# ROMmulti_final_rev01.net
KiCad netlist of a schematic drawn in EAGLE
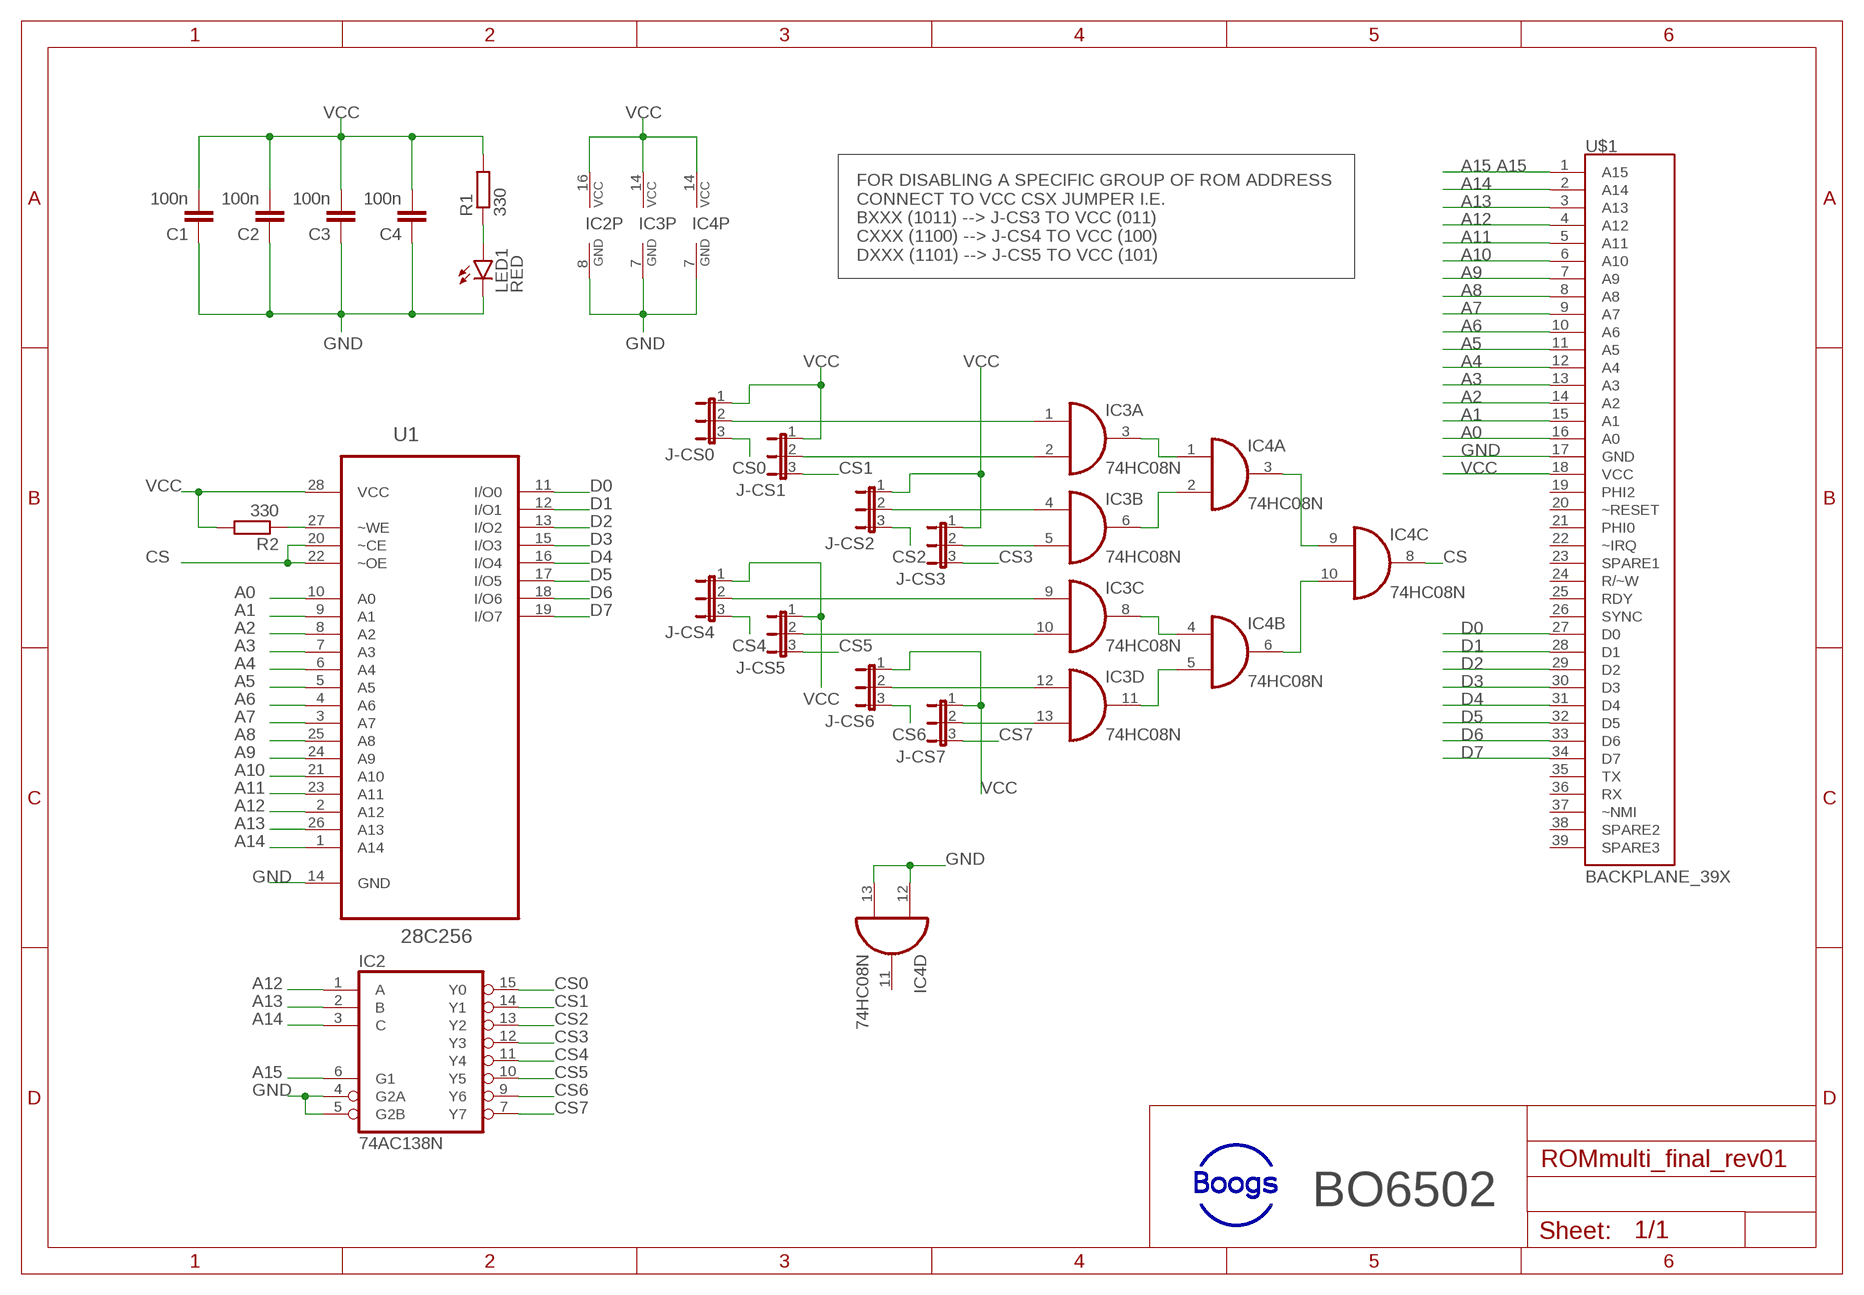
[diagram p0: schematic, sheet 1]

(export (version "E")
  (design (tool "Eeschema 10.0.6"))
  (components
    (comp (ref "C1")
      (value "100n")
      (footprint "eagle-import:C025-025X050")
      (libsource (lib "eagle-import") (part "C-EU025-025X050"))
    )
    (comp (ref "C2")
      (value "100n")
      (footprint "eagle-import:C025-025X050")
      (libsource (lib "eagle-import") (part "C-EU025-025X050"))
    )
    (comp (ref "C3")
      (value "100n")
      (footprint "eagle-import:C025-025X050")
      (libsource (lib "eagle-import") (part "C-EU025-025X050"))
    )
    (comp (ref "C4")
      (value "100n")
      (footprint "eagle-import:C025-025X050")
      (libsource (lib "eagle-import") (part "C-EU025-025X050"))
    )
    (comp (ref "IC2")
      (value "74AC138N")
      (footprint "eagle-import:DIL16")
      (libsource (lib "eagle-import") (part "74138NAC"))
    )
    (comp (ref "IC3")
      (value "74HC08N")
      (footprint "eagle-import:DIL14")
      (libsource (lib "eagle-import") (part "7408NHC"))
    )
    (comp (ref "IC4")
      (value "74HC08N")
      (footprint "eagle-import:DIL14")
      (libsource (lib "eagle-import") (part "7408NHC"))
    )
    (comp (ref "J-CS0")
      (value "J-CS0")
      (footprint "eagle-import:JP2")
      (libsource (lib "eagle-import") (part "JP2E"))
    )
    (comp (ref "J-CS1")
      (value "J-CS1")
      (footprint "eagle-import:JP2")
      (libsource (lib "eagle-import") (part "JP2E"))
    )
    (comp (ref "J-CS2")
      (value "J-CS2")
      (footprint "eagle-import:JP2")
      (libsource (lib "eagle-import") (part "JP2E"))
    )
    (comp (ref "J-CS3")
      (value "J-CS3")
      (footprint "eagle-import:JP2")
      (libsource (lib "eagle-import") (part "JP2E"))
    )
    (comp (ref "J-CS4")
      (value "J-CS4")
      (footprint "eagle-import:JP2")
      (libsource (lib "eagle-import") (part "JP2E"))
    )
    (comp (ref "J-CS5")
      (value "J-CS5")
      (footprint "eagle-import:JP2")
      (libsource (lib "eagle-import") (part "JP2E"))
    )
    (comp (ref "J-CS6")
      (value "J-CS6")
      (footprint "eagle-import:JP2")
      (libsource (lib "eagle-import") (part "JP2E"))
    )
    (comp (ref "J-CS7")
      (value "J-CS7")
      (footprint "eagle-import:JP2")
      (libsource (lib "eagle-import") (part "JP2E"))
    )
    (comp (ref "LED1")
      (value "RED")
      (footprint "eagle-import:LED5MM")
      (libsource (lib "eagle-import") (part "LED5MM"))
    )
    (comp (ref "R1")
      (value "330")
      (footprint "eagle-import:0207_10")
      (libsource (lib "eagle-import") (part "R-EU_0207/10"))
    )
    (comp (ref "R2")
      (value "330")
      (footprint "eagle-import:0207_10")
      (libsource (lib "eagle-import") (part "R-EU_0207/10"))
    )
    (comp (ref "U$1")
      (value "BACKPLANE_39X")
      (footprint "eagle-import:BP_39X")
      (fields (field (name "A15") "A15"))
      (libsource (lib "eagle-import") (part "BACKPLANE_39X"))
    )
    (comp (ref "U1")
      (value "28C256")
      (footprint "eagle-import:DIP254P1524X482-28")
      (fields (field (name "MF") "Microchip") (field (name "MP") "AT28C256-15PU"))
      (libsource (lib "eagle-import") (part "AT28C256-15PU"))
    )
  )
  (nets
    (net (code "1") (name "/A0") (class "Default")
      (node (ref "U$1") (pin "16") (pinfunction "A0_16") (pintype "bidirectional"))
      (node (ref "U1") (pin "10") (pinfunction "A0_10") (pintype "input"))
    )
    (net (code "2") (name "/A1") (class "Default")
      (node (ref "U$1") (pin "15") (pinfunction "A1_15") (pintype "bidirectional"))
      (node (ref "U1") (pin "9") (pinfunction "A1_9") (pintype "input"))
    )
    (net (code "3") (name "/A2") (class "Default")
      (node (ref "U$1") (pin "14") (pinfunction "A2_14") (pintype "bidirectional"))
      (node (ref "U1") (pin "8") (pinfunction "A2_8") (pintype "input"))
    )
    (net (code "4") (name "/A3") (class "Default")
      (node (ref "U$1") (pin "13") (pinfunction "A3_13") (pintype "bidirectional"))
      (node (ref "U1") (pin "7") (pinfunction "A3_7") (pintype "input"))
    )
    (net (code "5") (name "/A4") (class "Default")
      (node (ref "U$1") (pin "12") (pinfunction "A4_12") (pintype "bidirectional"))
      (node (ref "U1") (pin "6") (pinfunction "A4_6") (pintype "input"))
    )
    (net (code "6") (name "/A5") (class "Default")
      (node (ref "U$1") (pin "11") (pinfunction "A5_11") (pintype "bidirectional"))
      (node (ref "U1") (pin "5") (pinfunction "A5_5") (pintype "input"))
    )
    (net (code "7") (name "/A6") (class "Default")
      (node (ref "U$1") (pin "10") (pinfunction "A6_10") (pintype "bidirectional"))
      (node (ref "U1") (pin "4") (pinfunction "A6_4") (pintype "input"))
    )
    (net (code "8") (name "/A7") (class "Default")
      (node (ref "U$1") (pin "9") (pinfunction "A7_9") (pintype "bidirectional"))
      (node (ref "U1") (pin "3") (pinfunction "A7_3") (pintype "input"))
    )
    (net (code "9") (name "/A8") (class "Default")
      (node (ref "U$1") (pin "8") (pinfunction "A8_8") (pintype "bidirectional"))
      (node (ref "U1") (pin "25") (pinfunction "A8_25") (pintype "input"))
    )
    (net (code "10") (name "/A9") (class "Default")
      (node (ref "U$1") (pin "7") (pinfunction "A9_7") (pintype "bidirectional"))
      (node (ref "U1") (pin "24") (pinfunction "A9_24") (pintype "input"))
    )
    (net (code "11") (name "/A10") (class "Default")
      (node (ref "U$1") (pin "6") (pinfunction "A10_6") (pintype "bidirectional"))
      (node (ref "U1") (pin "21") (pinfunction "A10_21") (pintype "input"))
    )
    (net (code "12") (name "/A11") (class "Default")
      (node (ref "U$1") (pin "5") (pinfunction "A11_5") (pintype "bidirectional"))
      (node (ref "U1") (pin "23") (pinfunction "A11_23") (pintype "input"))
    )
    (net (code "13") (name "/A12") (class "Default")
      (node (ref "IC2") (pin "1") (pinfunction "A_1") (pintype "input"))
      (node (ref "U$1") (pin "4") (pinfunction "A12_4") (pintype "bidirectional"))
      (node (ref "U1") (pin "2") (pinfunction "A12_2") (pintype "input"))
    )
    (net (code "14") (name "/A13") (class "Default")
      (node (ref "IC2") (pin "2") (pinfunction "B_2") (pintype "input"))
      (node (ref "U$1") (pin "3") (pinfunction "A13_3") (pintype "bidirectional"))
      (node (ref "U1") (pin "26") (pinfunction "A13_26") (pintype "input"))
    )
    (net (code "15") (name "/A14") (class "Default")
      (node (ref "IC2") (pin "3") (pinfunction "C_3") (pintype "input"))
      (node (ref "U$1") (pin "2") (pinfunction "A14_2") (pintype "bidirectional"))
      (node (ref "U1") (pin "1") (pinfunction "A14_1") (pintype "input"))
    )
    (net (code "16") (name "/A15") (class "Default")
      (node (ref "IC2") (pin "6") (pinfunction "G1_6") (pintype "input"))
      (node (ref "U$1") (pin "1") (pinfunction "A15_1") (pintype "bidirectional"))
    )
    (net (code "17") (name "/CS") (class "Default")
      (node (ref "IC4") (pin "8") (pinfunction "O_8") (pintype "output"))
      (node (ref "U1") (pin "20") (pinfunction "~{CE}_20") (pintype "input"))
      (node (ref "U1") (pin "22") (pinfunction "~{OE}_22") (pintype "input"))
    )
    (net (code "18") (name "/CS0") (class "Default")
      (node (ref "IC2") (pin "15") (pinfunction "Y0_15") (pintype "output"))
      (node (ref "J-CS0") (pin "3") (pinfunction "3_3") (pintype "passive"))
    )
    (net (code "19") (name "/CS1") (class "Default")
      (node (ref "IC2") (pin "14") (pinfunction "Y1_14") (pintype "output"))
      (node (ref "J-CS1") (pin "3") (pinfunction "3_3") (pintype "passive"))
    )
    (net (code "20") (name "/CS2") (class "Default")
      (node (ref "IC2") (pin "13") (pinfunction "Y2_13") (pintype "output"))
      (node (ref "J-CS2") (pin "3") (pinfunction "3_3") (pintype "passive"))
    )
    (net (code "21") (name "/CS3") (class "Default")
      (node (ref "IC2") (pin "12") (pinfunction "Y3_12") (pintype "output"))
      (node (ref "J-CS3") (pin "3") (pinfunction "3_3") (pintype "passive"))
    )
    (net (code "22") (name "/CS4") (class "Default")
      (node (ref "IC2") (pin "11") (pinfunction "Y4_11") (pintype "output"))
      (node (ref "J-CS4") (pin "3") (pinfunction "3_3") (pintype "passive"))
    )
    (net (code "23") (name "/CS5") (class "Default")
      (node (ref "IC2") (pin "10") (pinfunction "Y5_10") (pintype "output"))
      (node (ref "J-CS5") (pin "3") (pinfunction "3_3") (pintype "passive"))
    )
    (net (code "24") (name "/CS6") (class "Default")
      (node (ref "IC2") (pin "9") (pinfunction "Y6_9") (pintype "output"))
      (node (ref "J-CS6") (pin "3") (pinfunction "3_3") (pintype "passive"))
    )
    (net (code "25") (name "/CS7") (class "Default")
      (node (ref "IC2") (pin "7") (pinfunction "Y7_7") (pintype "output"))
      (node (ref "J-CS7") (pin "3") (pinfunction "3_3") (pintype "passive"))
    )
    (net (code "26") (name "/D0") (class "Default")
      (node (ref "U$1") (pin "27") (pinfunction "D0_27") (pintype "bidirectional"))
      (node (ref "U1") (pin "11") (pinfunction "I/O0_11") (pintype "bidirectional"))
    )
    (net (code "27") (name "/D1") (class "Default")
      (node (ref "U$1") (pin "28") (pinfunction "D1_28") (pintype "bidirectional"))
      (node (ref "U1") (pin "12") (pinfunction "I/O1_12") (pintype "bidirectional"))
    )
    (net (code "28") (name "/D2") (class "Default")
      (node (ref "U$1") (pin "29") (pinfunction "D2_29") (pintype "bidirectional"))
      (node (ref "U1") (pin "13") (pinfunction "I/O2_13") (pintype "bidirectional"))
    )
    (net (code "29") (name "/D3") (class "Default")
      (node (ref "U$1") (pin "30") (pinfunction "D3_30") (pintype "bidirectional"))
      (node (ref "U1") (pin "15") (pinfunction "I/O3_15") (pintype "bidirectional"))
    )
    (net (code "30") (name "/D4") (class "Default")
      (node (ref "U$1") (pin "31") (pinfunction "D4_31") (pintype "bidirectional"))
      (node (ref "U1") (pin "16") (pinfunction "I/O4_16") (pintype "bidirectional"))
    )
    (net (code "31") (name "/D5") (class "Default")
      (node (ref "U$1") (pin "32") (pinfunction "D5_32") (pintype "bidirectional"))
      (node (ref "U1") (pin "17") (pinfunction "I/O5_17") (pintype "bidirectional"))
    )
    (net (code "32") (name "/D6") (class "Default")
      (node (ref "U$1") (pin "33") (pinfunction "D6_33") (pintype "bidirectional"))
      (node (ref "U1") (pin "18") (pinfunction "I/O6_18") (pintype "bidirectional"))
    )
    (net (code "33") (name "/D7") (class "Default")
      (node (ref "U$1") (pin "34") (pinfunction "D7_34") (pintype "bidirectional"))
      (node (ref "U1") (pin "19") (pinfunction "I/O7_19") (pintype "bidirectional"))
    )
    (net (code "34") (name "/GND") (class "Default")
      (node (ref "C1") (pin "1") (pinfunction "1_1") (pintype "passive"))
      (node (ref "C2") (pin "1") (pinfunction "1_1") (pintype "passive"))
      (node (ref "C3") (pin "1") (pinfunction "1_1") (pintype "passive"))
      (node (ref "C4") (pin "1") (pinfunction "1_1") (pintype "passive"))
      (node (ref "IC2") (pin "4") (pinfunction "G2A_4") (pintype "input"))
      (node (ref "IC2") (pin "5") (pinfunction "G2B_5") (pintype "input"))
      (node (ref "IC2") (pin "8") (pinfunction "GND_8") (pintype "power_in"))
      (node (ref "IC3") (pin "7") (pinfunction "GND_7") (pintype "power_in"))
      (node (ref "IC4") (pin "12") (pinfunction "I0_12") (pintype "input"))
      (node (ref "IC4") (pin "13") (pinfunction "I1_13") (pintype "input"))
      (node (ref "IC4") (pin "7") (pinfunction "GND_7") (pintype "power_in"))
      (node (ref "LED1") (pin "K") (pinfunction "C_K") (pintype "passive"))
      (node (ref "U$1") (pin "17") (pinfunction "GND_17") (pintype "bidirectional"))
      (node (ref "U1") (pin "14") (pinfunction "GND_14") (pintype "passive"))
    )
    (net (code "35") (name "/VCC") (class "Default")
      (node (ref "C1") (pin "2") (pinfunction "2_2") (pintype "passive"))
      (node (ref "C2") (pin "2") (pinfunction "2_2") (pintype "passive"))
      (node (ref "C3") (pin "2") (pinfunction "2_2") (pintype "passive"))
      (node (ref "C4") (pin "2") (pinfunction "2_2") (pintype "passive"))
      (node (ref "IC2") (pin "16") (pinfunction "VCC_16") (pintype "power_in"))
      (node (ref "IC3") (pin "14") (pinfunction "VCC_14") (pintype "power_in"))
      (node (ref "IC4") (pin "14") (pinfunction "VCC_14") (pintype "power_in"))
      (node (ref "J-CS0") (pin "1") (pinfunction "1_1") (pintype "passive"))
      (node (ref "J-CS1") (pin "1") (pinfunction "1_1") (pintype "passive"))
      (node (ref "J-CS2") (pin "1") (pinfunction "1_1") (pintype "passive"))
      (node (ref "J-CS3") (pin "1") (pinfunction "1_1") (pintype "passive"))
      (node (ref "J-CS4") (pin "1") (pinfunction "1_1") (pintype "passive"))
      (node (ref "J-CS5") (pin "1") (pinfunction "1_1") (pintype "passive"))
      (node (ref "J-CS6") (pin "1") (pinfunction "1_1") (pintype "passive"))
      (node (ref "J-CS7") (pin "1") (pinfunction "1_1") (pintype "passive"))
      (node (ref "R1") (pin "2") (pinfunction "2_2") (pintype "passive"))
      (node (ref "R2") (pin "2") (pinfunction "2_2") (pintype "passive"))
      (node (ref "U$1") (pin "18") (pinfunction "VCC_18") (pintype "bidirectional"))
      (node (ref "U1") (pin "28") (pinfunction "VCC_28") (pintype "power_in"))
    )
    (net (code "36") (name "Net-(IC3A-I0)") (class "Default")
      (node (ref "IC3") (pin "1") (pinfunction "I0_1") (pintype "input"))
      (node (ref "J-CS0") (pin "2") (pinfunction "2_2") (pintype "passive"))
    )
    (net (code "37") (name "Net-(IC3A-I1)") (class "Default")
      (node (ref "IC3") (pin "2") (pinfunction "I1_2") (pintype "input"))
      (node (ref "J-CS1") (pin "2") (pinfunction "2_2") (pintype "passive"))
    )
    (net (code "38") (name "Net-(IC3A-O)") (class "Default")
      (node (ref "IC3") (pin "3") (pinfunction "O_3") (pintype "output"))
      (node (ref "IC4") (pin "1") (pinfunction "I0_1") (pintype "input"))
    )
    (net (code "39") (name "Net-(IC3B-I0)") (class "Default")
      (node (ref "IC3") (pin "4") (pinfunction "I0_4") (pintype "input"))
      (node (ref "J-CS2") (pin "2") (pinfunction "2_2") (pintype "passive"))
    )
    (net (code "40") (name "Net-(IC3B-I1)") (class "Default")
      (node (ref "IC3") (pin "5") (pinfunction "I1_5") (pintype "input"))
      (node (ref "J-CS3") (pin "2") (pinfunction "2_2") (pintype "passive"))
    )
    (net (code "41") (name "Net-(IC3B-O)") (class "Default")
      (node (ref "IC3") (pin "6") (pinfunction "O_6") (pintype "output"))
      (node (ref "IC4") (pin "2") (pinfunction "I1_2") (pintype "input"))
    )
    (net (code "42") (name "Net-(IC3C-I0)") (class "Default")
      (node (ref "IC3") (pin "9") (pinfunction "I0_9") (pintype "input"))
      (node (ref "J-CS4") (pin "2") (pinfunction "2_2") (pintype "passive"))
    )
    (net (code "43") (name "Net-(IC3C-I1)") (class "Default")
      (node (ref "IC3") (pin "10") (pinfunction "I1_10") (pintype "input"))
      (node (ref "J-CS5") (pin "2") (pinfunction "2_2") (pintype "passive"))
    )
    (net (code "44") (name "Net-(IC3C-O)") (class "Default")
      (node (ref "IC3") (pin "8") (pinfunction "O_8") (pintype "output"))
      (node (ref "IC4") (pin "4") (pinfunction "I0_4") (pintype "input"))
    )
    (net (code "45") (name "Net-(IC3D-I0)") (class "Default")
      (node (ref "IC3") (pin "12") (pinfunction "I0_12") (pintype "input"))
      (node (ref "J-CS6") (pin "2") (pinfunction "2_2") (pintype "passive"))
    )
    (net (code "46") (name "Net-(IC3D-I1)") (class "Default")
      (node (ref "IC3") (pin "13") (pinfunction "I1_13") (pintype "input"))
      (node (ref "J-CS7") (pin "2") (pinfunction "2_2") (pintype "passive"))
    )
    (net (code "47") (name "Net-(IC3D-O)") (class "Default")
      (node (ref "IC3") (pin "11") (pinfunction "O_11") (pintype "output"))
      (node (ref "IC4") (pin "5") (pinfunction "I1_5") (pintype "input"))
    )
    (net (code "48") (name "Net-(IC4A-O)") (class "Default")
      (node (ref "IC4") (pin "3") (pinfunction "O_3") (pintype "output"))
      (node (ref "IC4") (pin "9") (pinfunction "I0_9") (pintype "input"))
    )
    (net (code "49") (name "Net-(IC4B-O)") (class "Default")
      (node (ref "IC4") (pin "10") (pinfunction "I1_10") (pintype "input"))
      (node (ref "IC4") (pin "6") (pinfunction "O_6") (pintype "output"))
    )
    (net (code "50") (name "Net-(LED1-PadA)") (class "Default")
      (node (ref "LED1") (pin "A") (pinfunction "A_A") (pintype "passive"))
      (node (ref "R1") (pin "1") (pinfunction "1_1") (pintype "passive"))
    )
    (net (code "51") (name "Net-(U1-~{WE})") (class "Default")
      (node (ref "R2") (pin "1") (pinfunction "1_1") (pintype "passive"))
      (node (ref "U1") (pin "27") (pinfunction "~{WE}_27") (pintype "input"))
    )
    (net (code "52") (name "unconnected-(IC4D-O-Pad11)") (class "Default")
      (node (ref "IC4") (pin "11") (pinfunction "O_11") (pintype "output"))
    )
    (net (code "53") (name "unconnected-(U$1-PHI0-Pad21)") (class "Default")
      (node (ref "U$1") (pin "21") (pinfunction "PHI0_21") (pintype "bidirectional"))
    )
    (net (code "54") (name "unconnected-(U$1-PHI2-Pad19)") (class "Default")
      (node (ref "U$1") (pin "19") (pinfunction "PHI2_19") (pintype "bidirectional"))
    )
    (net (code "55") (name "unconnected-(U$1-RDY-Pad25)") (class "Default")
      (node (ref "U$1") (pin "25") (pinfunction "RDY_25") (pintype "bidirectional"))
    )
    (net (code "56") (name "unconnected-(U$1-RX-Pad36)") (class "Default")
      (node (ref "U$1") (pin "36") (pinfunction "RX_36") (pintype "bidirectional"))
    )
    (net (code "57") (name "unconnected-(U$1-R{slash}~{W}-Pad24)") (class "Default")
      (node (ref "U$1") (pin "24") (pinfunction "R/~{W}_24") (pintype "bidirectional"))
    )
    (net (code "58") (name "unconnected-(U$1-SPARE1-Pad23)") (class "Default")
      (node (ref "U$1") (pin "23") (pinfunction "SPARE1_23") (pintype "bidirectional"))
    )
    (net (code "59") (name "unconnected-(U$1-SPARE2-Pad38)") (class "Default")
      (node (ref "U$1") (pin "38") (pinfunction "SPARE2_38") (pintype "bidirectional"))
    )
    (net (code "60") (name "unconnected-(U$1-SPARE3-Pad39)") (class "Default")
      (node (ref "U$1") (pin "39") (pinfunction "SPARE3_39") (pintype "bidirectional"))
    )
    (net (code "61") (name "unconnected-(U$1-SYNC-Pad26)") (class "Default")
      (node (ref "U$1") (pin "26") (pinfunction "SYNC_26") (pintype "bidirectional"))
    )
    (net (code "62") (name "unconnected-(U$1-TX-Pad35)") (class "Default")
      (node (ref "U$1") (pin "35") (pinfunction "TX_35") (pintype "bidirectional"))
    )
    (net (code "63") (name "unconnected-(U$1-~{IRQ}-Pad22)") (class "Default")
      (node (ref "U$1") (pin "22") (pinfunction "~{IRQ}_22") (pintype "bidirectional"))
    )
    (net (code "64") (name "unconnected-(U$1-~{NMI}-Pad37)") (class "Default")
      (node (ref "U$1") (pin "37") (pinfunction "~{NMI}_37") (pintype "bidirectional"))
    )
    (net (code "65") (name "unconnected-(U$1-~{RESET}-Pad20)") (class "Default")
      (node (ref "U$1") (pin "20") (pinfunction "~{RESET}_20") (pintype "bidirectional"))
    )
  )
)
